# Rpi_GPIO.net
KiCad netlist of a schematic drawn in Altium Designer
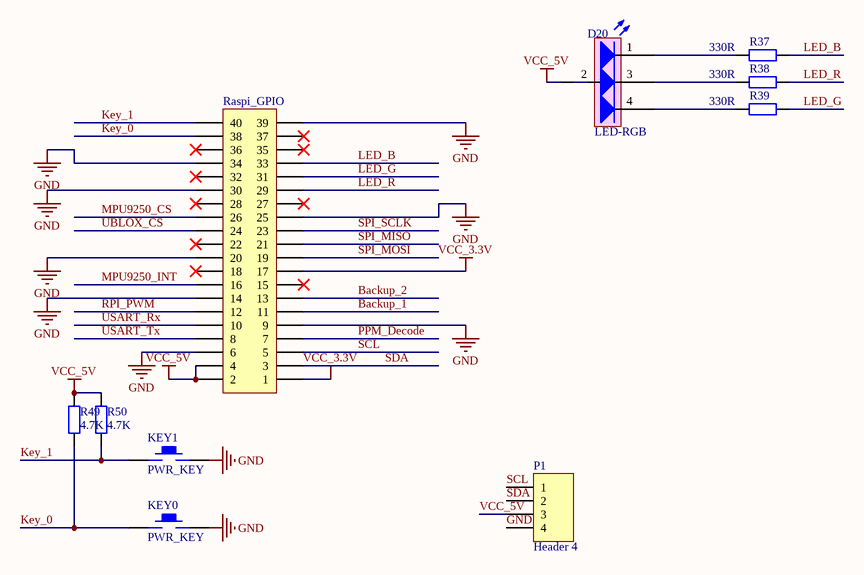
[diagram p0: Rpi_GPIO.SchDoc]

(export (version "E")
  (design (tool "Eeschema 10.0.6"))
  (components
    (comp (ref "D20")
      (value "LED-RGB")
      (footprint "5050-ok:LED_5050_RGB")
      (description "三基色LED")
      (fields (field (name "PUBLISHER") "Altium Limited"))
      (libsource (lib "fszhang") (part "LED-RGB"))
    )
    (comp (ref "KEY0")
      (value "PWR_KEY")
      (footprint "KEY_M")
      (libsource (lib "ATK-SIM900A GSM模块封装库") (part "KEY_M"))
    )
    (comp (ref "KEY1")
      (value "PWR_KEY")
      (footprint "KEY_M")
      (libsource (lib "ATK-SIM900A GSM模块封装库") (part "KEY_M"))
    )
    (comp (ref "P1")
      (value "Header 4")
      (footprint "HDR1X4")
      (description "Header, 4-Pin")
      (fields (field (name "PUBLISHER") "Altium Limited"))
      (libsource (lib "Miscellaneous Connectors") (part "Header 4"))
    )
    (comp (ref "R37")
      (value "330R")
      (footprint "3.5TFTLCD封装库:0805")
      (description "Resistor")
      (fields (field (name "Comment") "Res2") (field (name "PUBLISHER") "Altium Limited"))
      (libsource (lib "Miscellaneous Devices") (part "Res2"))
    )
    (comp (ref "R38")
      (value "330R")
      (footprint "3.5TFTLCD封装库:0805")
      (description "Resistor")
      (fields (field (name "Comment") "Res2") (field (name "PUBLISHER") "Altium Limited"))
      (libsource (lib "Miscellaneous Devices") (part "Res2"))
    )
    (comp (ref "R39")
      (value "330R")
      (footprint "3.5TFTLCD封装库:0805")
      (description "Resistor")
      (fields (field (name "Comment") "Res2") (field (name "PUBLISHER") "Altium Limited"))
      (libsource (lib "Miscellaneous Devices") (part "Res2"))
    )
    (comp (ref "R49")
      (value "4.7K")
      (footprint "3.5TFTLCD封装库:0805")
      (description "Resistor")
      (fields (field (name "Comment") "Res2") (field (name "PUBLISHER") "Altium Limited"))
      (libsource (lib "") (part "Res2_1"))
    )
    (comp (ref "R50")
      (value "4.7K")
      (footprint "3.5TFTLCD封装库:0805")
      (description "Resistor")
      (fields (field (name "Comment") "Res2") (field (name "PUBLISHER") "Altium Limited"))
      (libsource (lib "") (part "Res2_1"))
    )
    (comp (ref "Raspi_GPIO")
      (value "Header 20X2")
      (footprint "HDR2X20")
      (description "Header, 20-Pin, Dual row")
      (fields (field (name "PUBLISHER") "Altium Limited"))
      (libsource (lib "Miscellaneous Connectors") (part "Header 20X2"))
    )
  )
  (nets
    (net (code "1") (name "/Backup_1") (class "Default")
      (node (ref "Raspi_GPIO") (pin "11") (pinfunction "11_11") (pintype "passive"))
    )
    (net (code "2") (name "/Backup_2") (class "Default")
      (node (ref "Raspi_GPIO") (pin "13") (pinfunction "13_13") (pintype "passive"))
    )
    (net (code "3") (name "/Key_0") (class "Default")
      (node (ref "KEY0") (pin "1") (pinfunction "1_1") (pintype "passive"))
      (node (ref "R49") (pin "2") (pinfunction "2_2") (pintype "passive"))
      (node (ref "Raspi_GPIO") (pin "38") (pinfunction "38_38") (pintype "passive"))
    )
    (net (code "4") (name "/Key_1") (class "Default")
      (node (ref "KEY1") (pin "1") (pinfunction "1_1") (pintype "passive"))
      (node (ref "R50") (pin "2") (pinfunction "2_2") (pintype "passive"))
      (node (ref "Raspi_GPIO") (pin "40") (pinfunction "40_40") (pintype "passive"))
    )
    (net (code "5") (name "/LED_B") (class "Default")
      (node (ref "R37") (pin "1") (pinfunction "1_1") (pintype "passive"))
      (node (ref "Raspi_GPIO") (pin "33") (pinfunction "33_33") (pintype "passive"))
    )
    (net (code "6") (name "/LED_G") (class "Default")
      (node (ref "R39") (pin "1") (pinfunction "1_1") (pintype "passive"))
      (node (ref "Raspi_GPIO") (pin "31") (pinfunction "31_31") (pintype "passive"))
    )
    (net (code "7") (name "/LED_R") (class "Default")
      (node (ref "R38") (pin "1") (pinfunction "1_1") (pintype "passive"))
      (node (ref "Raspi_GPIO") (pin "29") (pinfunction "29_29") (pintype "passive"))
    )
    (net (code "8") (name "/MPU9250_CS") (class "Default")
      (node (ref "Raspi_GPIO") (pin "26") (pinfunction "26_26") (pintype "passive"))
    )
    (net (code "9") (name "/MPU9250_INT") (class "Default")
      (node (ref "Raspi_GPIO") (pin "16") (pinfunction "16_16") (pintype "passive"))
    )
    (net (code "10") (name "/PPM_Decode") (class "Default")
      (node (ref "Raspi_GPIO") (pin "7") (pinfunction "7_7") (pintype "passive"))
    )
    (net (code "11") (name "/RPI_PWM") (class "Default")
      (node (ref "Raspi_GPIO") (pin "12") (pinfunction "12_12") (pintype "passive"))
    )
    (net (code "12") (name "/SCL") (class "Default")
      (node (ref "P1") (pin "1") (pinfunction "1_1") (pintype "passive"))
      (node (ref "Raspi_GPIO") (pin "5") (pinfunction "5_5") (pintype "passive"))
    )
    (net (code "13") (name "/SDA") (class "Default")
      (node (ref "P1") (pin "2") (pinfunction "2_2") (pintype "passive"))
      (node (ref "Raspi_GPIO") (pin "3") (pinfunction "3_3") (pintype "passive"))
    )
    (net (code "14") (name "/SPI_MISO") (class "Default")
      (node (ref "Raspi_GPIO") (pin "21") (pinfunction "21_21") (pintype "passive"))
    )
    (net (code "15") (name "/SPI_MOSI") (class "Default")
      (node (ref "Raspi_GPIO") (pin "19") (pinfunction "19_19") (pintype "passive"))
    )
    (net (code "16") (name "/SPI_SCLK") (class "Default")
      (node (ref "Raspi_GPIO") (pin "23") (pinfunction "23_23") (pintype "passive"))
    )
    (net (code "17") (name "/UBLOX_CS") (class "Default")
      (node (ref "Raspi_GPIO") (pin "24") (pinfunction "24_24") (pintype "passive"))
    )
    (net (code "18") (name "/USART_Rx") (class "Default")
      (node (ref "Raspi_GPIO") (pin "10") (pinfunction "10_10") (pintype "passive"))
    )
    (net (code "19") (name "/USART_Tx") (class "Default")
      (node (ref "Raspi_GPIO") (pin "8") (pinfunction "8_8") (pintype "passive"))
    )
    (net (code "20") (name "GND") (class "Default")
      (node (ref "KEY0") (pin "2") (pinfunction "2_2") (pintype "passive"))
      (node (ref "KEY1") (pin "2") (pinfunction "2_2") (pintype "passive"))
      (node (ref "P1") (pin "4") (pinfunction "4_4") (pintype "passive"))
      (node (ref "Raspi_GPIO") (pin "14") (pinfunction "14_14") (pintype "passive"))
      (node (ref "Raspi_GPIO") (pin "20") (pinfunction "20_20") (pintype "passive"))
      (node (ref "Raspi_GPIO") (pin "25") (pinfunction "25_25") (pintype "passive"))
      (node (ref "Raspi_GPIO") (pin "30") (pinfunction "30_30") (pintype "passive"))
      (node (ref "Raspi_GPIO") (pin "34") (pinfunction "34_34") (pintype "passive"))
      (node (ref "Raspi_GPIO") (pin "39") (pinfunction "39_39") (pintype "passive"))
      (node (ref "Raspi_GPIO") (pin "6") (pinfunction "6_6") (pintype "passive"))
      (node (ref "Raspi_GPIO") (pin "9") (pinfunction "9_9") (pintype "passive"))
    )
    (net (code "21") (name "Net-(D20-B)") (class "Default")
      (node (ref "D20") (pin "4") (pinfunction "B_4") (pintype "passive"))
      (node (ref "R39") (pin "2") (pinfunction "2_2") (pintype "passive"))
    )
    (net (code "22") (name "Net-(D20-G)") (class "Default")
      (node (ref "D20") (pin "3") (pinfunction "G_3") (pintype "passive"))
      (node (ref "R38") (pin "2") (pinfunction "2_2") (pintype "passive"))
    )
    (net (code "23") (name "Net-(D20-R)") (class "Default")
      (node (ref "D20") (pin "1") (pinfunction "R_1") (pintype "passive"))
      (node (ref "R37") (pin "2") (pinfunction "2_2") (pintype "passive"))
    )
    (net (code "24") (name "VCC_3.3V") (class "Default")
      (node (ref "Raspi_GPIO") (pin "1") (pinfunction "1_1") (pintype "passive"))
      (node (ref "Raspi_GPIO") (pin "17") (pinfunction "17_17") (pintype "passive"))
    )
    (net (code "25") (name "VCC_5V") (class "Default")
      (node (ref "D20") (pin "2") (pinfunction "A_2") (pintype "passive"))
      (node (ref "P1") (pin "3") (pinfunction "3_3") (pintype "passive"))
      (node (ref "R49") (pin "1") (pinfunction "1_1") (pintype "passive"))
      (node (ref "R50") (pin "1") (pinfunction "1_1") (pintype "passive"))
      (node (ref "Raspi_GPIO") (pin "2") (pinfunction "2_2") (pintype "passive"))
      (node (ref "Raspi_GPIO") (pin "4") (pinfunction "4_4") (pintype "passive"))
    )
    (net (code "26") (name "unconnected-(Raspi_GPIO-Pad15)") (class "Default")
      (node (ref "Raspi_GPIO") (pin "15") (pinfunction "15_15") (pintype "passive+no_connect"))
    )
    (net (code "27") (name "unconnected-(Raspi_GPIO-Pad18)") (class "Default")
      (node (ref "Raspi_GPIO") (pin "18") (pinfunction "18_18") (pintype "passive+no_connect"))
    )
    (net (code "28") (name "unconnected-(Raspi_GPIO-Pad22)") (class "Default")
      (node (ref "Raspi_GPIO") (pin "22") (pinfunction "22_22") (pintype "passive+no_connect"))
    )
    (net (code "29") (name "unconnected-(Raspi_GPIO-Pad27)") (class "Default")
      (node (ref "Raspi_GPIO") (pin "27") (pinfunction "27_27") (pintype "passive+no_connect"))
    )
    (net (code "30") (name "unconnected-(Raspi_GPIO-Pad28)") (class "Default")
      (node (ref "Raspi_GPIO") (pin "28") (pinfunction "28_28") (pintype "passive+no_connect"))
    )
    (net (code "31") (name "unconnected-(Raspi_GPIO-Pad32)") (class "Default")
      (node (ref "Raspi_GPIO") (pin "32") (pinfunction "32_32") (pintype "passive+no_connect"))
    )
    (net (code "32") (name "unconnected-(Raspi_GPIO-Pad35)") (class "Default")
      (node (ref "Raspi_GPIO") (pin "35") (pinfunction "35_35") (pintype "passive+no_connect"))
    )
    (net (code "33") (name "unconnected-(Raspi_GPIO-Pad36)") (class "Default")
      (node (ref "Raspi_GPIO") (pin "36") (pinfunction "36_36") (pintype "passive+no_connect"))
    )
    (net (code "34") (name "unconnected-(Raspi_GPIO-Pad37)") (class "Default")
      (node (ref "Raspi_GPIO") (pin "37") (pinfunction "37_37") (pintype "passive+no_connect"))
    )
  )
)
